# GMC-4_UBW_Loader.net
KiCad netlist of a schematic drawn in EAGLE
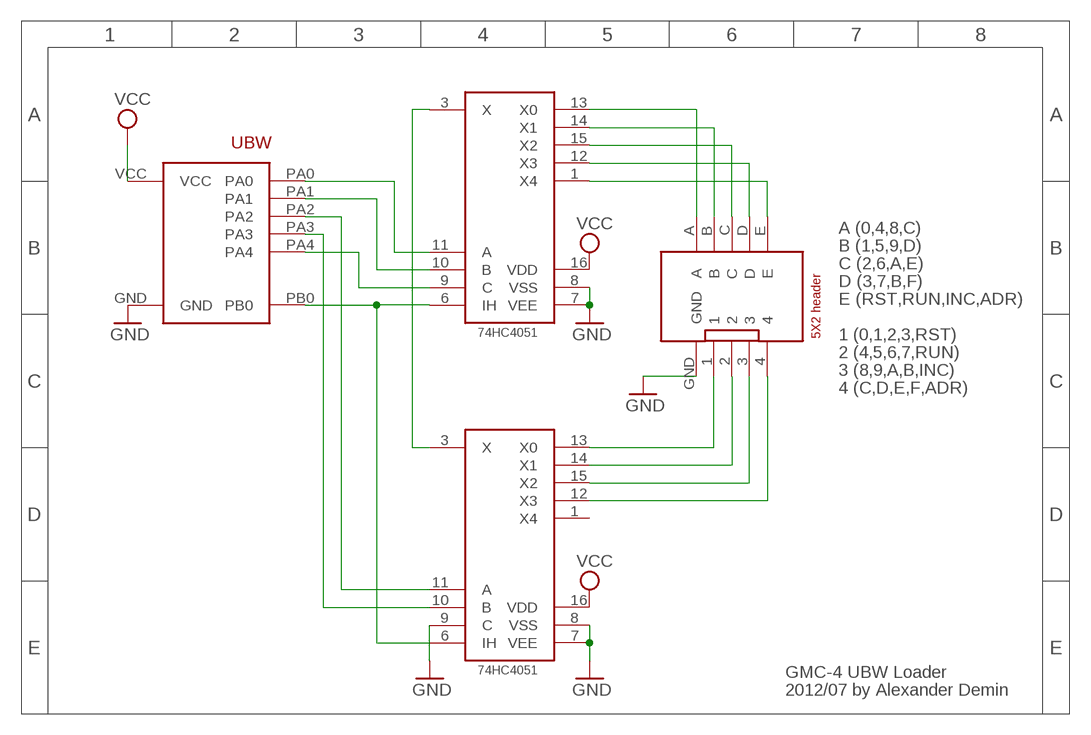
[diagram p0: schematic, sheet 1]

(export (version "E")
  (design (tool "Eeschema 10.0.6"))
  (components
    (comp (ref "U$1")
      (value "UBW")
      (footprint "eagle-import:UBW")
      (libsource (lib "eagle-import") (part "UBW"))
    )
    (comp (ref "U$2")
      (value "5X2")
      (footprint "eagle-import:5X2")
      (libsource (lib "eagle-import") (part "5X2"))
    )
    (comp (ref "U$3")
      (value "4051")
      (footprint "eagle-import:4051")
      (libsource (lib "eagle-import") (part "4051"))
    )
    (comp (ref "U$4")
      (value "4051")
      (footprint "eagle-import:4051")
      (libsource (lib "eagle-import") (part "4051"))
    )
  )
  (nets
    (net (code "1") (name "GND") (class "Default")
      (node (ref "U$1") (pin "GND") (pinfunction "GND_GND") (pintype "power_in"))
      (node (ref "U$2") (pin "GND") (pinfunction "GND_GND") (pintype "bidirectional"))
      (node (ref "U$3") (pin "7") (pinfunction "VEE_7") (pintype "bidirectional"))
      (node (ref "U$3") (pin "8") (pinfunction "VSS_8") (pintype "bidirectional"))
      (node (ref "U$4") (pin "7") (pinfunction "VEE_7") (pintype "bidirectional"))
      (node (ref "U$4") (pin "8") (pinfunction "VSS_8") (pintype "bidirectional"))
      (node (ref "U$4") (pin "9") (pinfunction "C_9") (pintype "bidirectional"))
    )
    (net (code "2") (name "Net-(U$3-A)") (class "Default")
      (node (ref "U$1") (pin "PA0") (pinfunction "PA0_PA0") (pintype "bidirectional"))
      (node (ref "U$3") (pin "11") (pinfunction "A_11") (pintype "bidirectional"))
    )
    (net (code "3") (name "Net-(U$3-B)") (class "Default")
      (node (ref "U$1") (pin "PA1") (pinfunction "PA1_PA1") (pintype "bidirectional"))
      (node (ref "U$3") (pin "10") (pinfunction "B_10") (pintype "bidirectional"))
    )
    (net (code "4") (name "Net-(U$3-C)") (class "Default")
      (node (ref "U$1") (pin "PA4") (pinfunction "PA4_PA4") (pintype "bidirectional"))
      (node (ref "U$3") (pin "9") (pinfunction "C_9") (pintype "bidirectional"))
    )
    (net (code "5") (name "Net-(U$3-IH)") (class "Default")
      (node (ref "U$1") (pin "PB0") (pinfunction "PB0_PB0") (pintype "bidirectional"))
      (node (ref "U$3") (pin "6") (pinfunction "IH_6") (pintype "bidirectional"))
      (node (ref "U$4") (pin "6") (pinfunction "IH_6") (pintype "bidirectional"))
    )
    (net (code "6") (name "Net-(U$3-X)") (class "Default")
      (node (ref "U$3") (pin "3") (pinfunction "X_3") (pintype "bidirectional"))
      (node (ref "U$4") (pin "3") (pinfunction "X_3") (pintype "bidirectional"))
    )
    (net (code "7") (name "Net-(U$3-X0)") (class "Default")
      (node (ref "U$2") (pin "A") (pinfunction "A_A") (pintype "bidirectional"))
      (node (ref "U$3") (pin "13") (pinfunction "X0_13") (pintype "bidirectional"))
    )
    (net (code "8") (name "Net-(U$3-X1)") (class "Default")
      (node (ref "U$2") (pin "B") (pinfunction "B_B") (pintype "bidirectional"))
      (node (ref "U$3") (pin "14") (pinfunction "X1_14") (pintype "bidirectional"))
    )
    (net (code "9") (name "Net-(U$3-X2)") (class "Default")
      (node (ref "U$2") (pin "C") (pinfunction "C_C") (pintype "bidirectional"))
      (node (ref "U$3") (pin "15") (pinfunction "X2_15") (pintype "bidirectional"))
    )
    (net (code "10") (name "Net-(U$3-X3)") (class "Default")
      (node (ref "U$2") (pin "D") (pinfunction "D_D") (pintype "bidirectional"))
      (node (ref "U$3") (pin "12") (pinfunction "X3_12") (pintype "bidirectional"))
    )
    (net (code "11") (name "Net-(U$3-X4)") (class "Default")
      (node (ref "U$2") (pin "E") (pinfunction "E_E") (pintype "bidirectional"))
      (node (ref "U$3") (pin "1") (pinfunction "X4_1") (pintype "bidirectional"))
    )
    (net (code "12") (name "Net-(U$4-A)") (class "Default")
      (node (ref "U$1") (pin "PA2") (pinfunction "PA2_PA2") (pintype "bidirectional"))
      (node (ref "U$4") (pin "11") (pinfunction "A_11") (pintype "bidirectional"))
    )
    (net (code "13") (name "Net-(U$4-B)") (class "Default")
      (node (ref "U$1") (pin "PA3") (pinfunction "PA3_PA3") (pintype "bidirectional"))
      (node (ref "U$4") (pin "10") (pinfunction "B_10") (pintype "bidirectional"))
    )
    (net (code "14") (name "Net-(U$4-X0)") (class "Default")
      (node (ref "U$2") (pin "1") (pinfunction "1_1") (pintype "bidirectional"))
      (node (ref "U$4") (pin "13") (pinfunction "X0_13") (pintype "bidirectional"))
    )
    (net (code "15") (name "Net-(U$4-X1)") (class "Default")
      (node (ref "U$2") (pin "2") (pinfunction "2_2") (pintype "bidirectional"))
      (node (ref "U$4") (pin "14") (pinfunction "X1_14") (pintype "bidirectional"))
    )
    (net (code "16") (name "Net-(U$4-X2)") (class "Default")
      (node (ref "U$2") (pin "3") (pinfunction "3_3") (pintype "bidirectional"))
      (node (ref "U$4") (pin "15") (pinfunction "X2_15") (pintype "bidirectional"))
    )
    (net (code "17") (name "Net-(U$4-X3)") (class "Default")
      (node (ref "U$2") (pin "4") (pinfunction "4_4") (pintype "bidirectional"))
      (node (ref "U$4") (pin "12") (pinfunction "X3_12") (pintype "bidirectional"))
    )
    (net (code "18") (name "VCC") (class "Default")
      (node (ref "U$1") (pin "VCC") (pinfunction "VCC_VCC") (pintype "power_in"))
      (node (ref "U$3") (pin "16") (pinfunction "VDD_16") (pintype "bidirectional"))
      (node (ref "U$4") (pin "16") (pinfunction "VDD_16") (pintype "bidirectional"))
    )
    (net (code "19") (name "unconnected-(U$4-X4-Pad1)") (class "Default")
      (node (ref "U$4") (pin "1") (pinfunction "X4_1") (pintype "bidirectional"))
    )
  )
)
